# LEDs_Sheet_2.net
KiCad netlist of a schematic drawn in Altium Designer
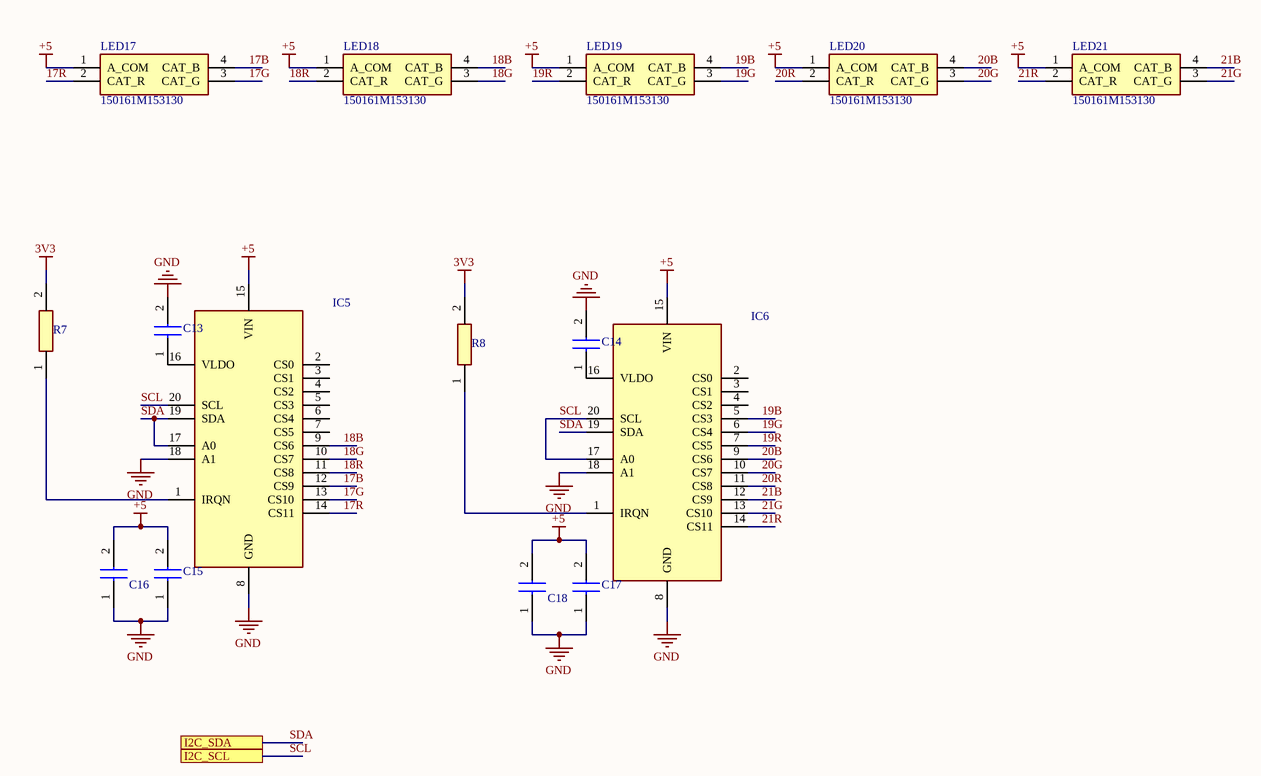
[diagram p0: LEDs_Sheet_2.SchDoc]

(export (version "E")
  (design (tool "Eeschema 10.0.6"))
  (components
    (comp (ref "C13")
      (value "C0402C105K9PAC")
      (footprint "SamacSys:CAPC1005X55N")
      (description "Capacitor")
      (fields (field (name "MOUSER PART NUMBER") "80-C0402C105K9PAC"))
      (libsource (lib "*") (part "C0402C105K9PAC"))
    )
    (comp (ref "C14")
      (value "C0402C105K9PAC")
      (footprint "SamacSys:CAPC1005X55N")
      (description "Capacitor")
      (fields (field (name "MOUSER PART NUMBER") "80-C0402C105K9PAC"))
      (libsource (lib "*") (part "C0402C105K9PAC"))
    )
    (comp (ref "C15")
      (value "C0402C105K9PAC")
      (footprint "SamacSys:CAPC1005X55N")
      (description "Capacitor")
      (fields (field (name "MOUSER PART NUMBER") "80-C0402C105K9PAC"))
      (libsource (lib "*") (part "C0402C105K9PAC"))
    )
    (comp (ref "C16")
      (value "C1005X7S1A225K050BC")
      (footprint "PcbLib:C1005_Commercial")
      (description "2µ2F 0402")
      (fields (field (name "MOUSER PART NUMBER") "810-C1005X7S1A225K"))
      (libsource (lib "Schlib") (part "C1005X7S1A225K050BC"))
    )
    (comp (ref "C17")
      (value "C0402C105K9PAC")
      (footprint "SamacSys:CAPC1005X55N")
      (description "Capacitor")
      (fields (field (name "MOUSER PART NUMBER") "80-C0402C105K9PAC"))
      (libsource (lib "*") (part "C0402C105K9PAC"))
    )
    (comp (ref "C18")
      (value "C1005X7S1A225K050BC")
      (footprint "PcbLib:C1005_Commercial")
      (description "2µ2F 0402")
      (fields (field (name "MOUSER PART NUMBER") "810-C1005X7S1A225K"))
      (libsource (lib "Schlib") (part "C1005X7S1A225K050BC"))
    )
    (comp (ref "IC5")
      (value "LED1202JR")
      (footprint "PcbLib:QFN20 3x3 (0,5mm pitch)")
      (description "Integrated Circuit")
      (fields (field (name "MOUSER PART NUMBER") "511-LED1202JR"))
      (libsource (lib "Schlib") (part "LED1202JR"))
    )
    (comp (ref "IC6")
      (value "LED1202JR")
      (footprint "PcbLib:QFN20 3x3 (0,5mm pitch)")
      (description "Integrated Circuit")
      (fields (field (name "MOUSER PART NUMBER") "511-LED1202JR"))
      (libsource (lib "Schlib") (part "LED1202JR"))
    )
    (comp (ref "LED17")
      (value "150161M153130")
      (footprint "PcbLib:150161M153130")
      (description "LED")
      (fields (field (name "MOUSER PART NUMBER") "710-150161M153130"))
      (libsource (lib "Schlib") (part "150161M153130"))
    )
    (comp (ref "LED18")
      (value "150161M153130")
      (footprint "PcbLib:150161M153130")
      (description "LED")
      (fields (field (name "MOUSER PART NUMBER") "710-150161M153130"))
      (libsource (lib "Schlib") (part "150161M153130"))
    )
    (comp (ref "LED19")
      (value "150161M153130")
      (footprint "PcbLib:150161M153130")
      (description "LED")
      (fields (field (name "MOUSER PART NUMBER") "710-150161M153130"))
      (libsource (lib "Schlib") (part "150161M153130"))
    )
    (comp (ref "LED20")
      (value "150161M153130")
      (footprint "PcbLib:150161M153130")
      (description "LED")
      (fields (field (name "MOUSER PART NUMBER") "710-150161M153130"))
      (libsource (lib "Schlib") (part "150161M153130"))
    )
    (comp (ref "LED21")
      (value "150161M153130")
      (footprint "PcbLib:150161M153130")
      (description "LED")
      (fields (field (name "MOUSER PART NUMBER") "710-150161M153130"))
      (libsource (lib "Schlib") (part "150161M153130"))
    )
    (comp (ref "R7")
      (value "MCS04020D1001BE000")
      (footprint "PcbLib:RESC1005X37N")
      (description "Resistor 1k 0402")
      (fields (field (name "MOUSER PART NUMBER") "594-MCS04020D1001BE0"))
      (libsource (lib "Schlib") (part "MCS04020D1001BE000"))
    )
    (comp (ref "R8")
      (value "MCS04020D1001BE000")
      (footprint "PcbLib:RESC1005X37N")
      (description "Resistor 1k 0402")
      (fields (field (name "MOUSER PART NUMBER") "594-MCS04020D1001BE0"))
      (libsource (lib "Schlib") (part "MCS04020D1001BE000"))
    )
  )
  (nets
    (net (code "1") (name "+5") (class "Default")
      (node (ref "C15") (pin "2") (pinfunction "2_2") (pintype "passive"))
      (node (ref "C16") (pin "2") (pinfunction "2_2") (pintype "passive"))
      (node (ref "C17") (pin "2") (pinfunction "2_2") (pintype "passive"))
      (node (ref "C18") (pin "2") (pinfunction "2_2") (pintype "passive"))
      (node (ref "IC5") (pin "15") (pinfunction "VIN_15") (pintype "passive"))
      (node (ref "IC6") (pin "15") (pinfunction "VIN_15") (pintype "passive"))
      (node (ref "LED17") (pin "1") (pinfunction "A_COM_1") (pintype "passive"))
      (node (ref "LED18") (pin "1") (pinfunction "A_COM_1") (pintype "passive"))
      (node (ref "LED19") (pin "1") (pinfunction "A_COM_1") (pintype "passive"))
      (node (ref "LED20") (pin "1") (pinfunction "A_COM_1") (pintype "passive"))
      (node (ref "LED21") (pin "1") (pinfunction "A_COM_1") (pintype "passive"))
    )
    (net (code "2") (name "/17B") (class "Default")
      (node (ref "IC5") (pin "12") (pinfunction "CS9_12") (pintype "passive"))
      (node (ref "LED17") (pin "4") (pinfunction "CAT_B_4") (pintype "passive"))
    )
    (net (code "3") (name "/17G") (class "Default")
      (node (ref "IC5") (pin "13") (pinfunction "CS10_13") (pintype "passive"))
      (node (ref "LED17") (pin "3") (pinfunction "CAT_G_3") (pintype "passive"))
    )
    (net (code "4") (name "/17R") (class "Default")
      (node (ref "IC5") (pin "14") (pinfunction "CS11_14") (pintype "passive"))
      (node (ref "LED17") (pin "2") (pinfunction "CAT_R_2") (pintype "passive"))
    )
    (net (code "5") (name "/18B") (class "Default")
      (node (ref "IC5") (pin "9") (pinfunction "CS6_9") (pintype "passive"))
      (node (ref "LED18") (pin "4") (pinfunction "CAT_B_4") (pintype "passive"))
    )
    (net (code "6") (name "/18G") (class "Default")
      (node (ref "IC5") (pin "10") (pinfunction "CS7_10") (pintype "passive"))
      (node (ref "LED18") (pin "3") (pinfunction "CAT_G_3") (pintype "passive"))
    )
    (net (code "7") (name "/18R") (class "Default")
      (node (ref "IC5") (pin "11") (pinfunction "CS8_11") (pintype "passive"))
      (node (ref "LED18") (pin "2") (pinfunction "CAT_R_2") (pintype "passive"))
    )
    (net (code "8") (name "/19B") (class "Default")
      (node (ref "IC6") (pin "5") (pinfunction "CS3_5") (pintype "passive"))
      (node (ref "LED19") (pin "4") (pinfunction "CAT_B_4") (pintype "passive"))
    )
    (net (code "9") (name "/19G") (class "Default")
      (node (ref "IC6") (pin "6") (pinfunction "CS4_6") (pintype "passive"))
      (node (ref "LED19") (pin "3") (pinfunction "CAT_G_3") (pintype "passive"))
    )
    (net (code "10") (name "/19R") (class "Default")
      (node (ref "IC6") (pin "7") (pinfunction "CS5_7") (pintype "passive"))
      (node (ref "LED19") (pin "2") (pinfunction "CAT_R_2") (pintype "passive"))
    )
    (net (code "11") (name "/20B") (class "Default")
      (node (ref "IC6") (pin "9") (pinfunction "CS6_9") (pintype "passive"))
      (node (ref "LED20") (pin "4") (pinfunction "CAT_B_4") (pintype "passive"))
    )
    (net (code "12") (name "/20G") (class "Default")
      (node (ref "IC6") (pin "10") (pinfunction "CS7_10") (pintype "passive"))
      (node (ref "LED20") (pin "3") (pinfunction "CAT_G_3") (pintype "passive"))
    )
    (net (code "13") (name "/20R") (class "Default")
      (node (ref "IC6") (pin "11") (pinfunction "CS8_11") (pintype "passive"))
      (node (ref "LED20") (pin "2") (pinfunction "CAT_R_2") (pintype "passive"))
    )
    (net (code "14") (name "/21B") (class "Default")
      (node (ref "IC6") (pin "12") (pinfunction "CS9_12") (pintype "passive"))
      (node (ref "LED21") (pin "4") (pinfunction "CAT_B_4") (pintype "passive"))
    )
    (net (code "15") (name "/21G") (class "Default")
      (node (ref "IC6") (pin "13") (pinfunction "CS10_13") (pintype "passive"))
      (node (ref "LED21") (pin "3") (pinfunction "CAT_G_3") (pintype "passive"))
    )
    (net (code "16") (name "/21R") (class "Default")
      (node (ref "IC6") (pin "14") (pinfunction "CS11_14") (pintype "passive"))
      (node (ref "LED21") (pin "2") (pinfunction "CAT_R_2") (pintype "passive"))
    )
    (net (code "17") (name "/SCL") (class "Default")
      (node (ref "IC5") (pin "20") (pinfunction "SCL_20") (pintype "passive"))
      (node (ref "IC6") (pin "17") (pinfunction "A0_17") (pintype "passive"))
      (node (ref "IC6") (pin "20") (pinfunction "SCL_20") (pintype "passive"))
    )
    (net (code "18") (name "/SDA") (class "Default")
      (node (ref "IC5") (pin "17") (pinfunction "A0_17") (pintype "passive"))
      (node (ref "IC5") (pin "19") (pinfunction "SDA_19") (pintype "passive"))
      (node (ref "IC6") (pin "19") (pinfunction "SDA_19") (pintype "passive"))
    )
    (net (code "19") (name "3V3") (class "Default")
      (node (ref "R7") (pin "2") (pinfunction "2_2") (pintype "passive"))
      (node (ref "R8") (pin "2") (pinfunction "2_2") (pintype "passive"))
    )
    (net (code "20") (name "GND") (class "Default")
      (node (ref "C13") (pin "2") (pinfunction "2_2") (pintype "passive"))
      (node (ref "C14") (pin "2") (pinfunction "2_2") (pintype "passive"))
      (node (ref "C15") (pin "1") (pinfunction "1_1") (pintype "passive"))
      (node (ref "C16") (pin "1") (pinfunction "1_1") (pintype "passive"))
      (node (ref "C17") (pin "1") (pinfunction "1_1") (pintype "passive"))
      (node (ref "C18") (pin "1") (pinfunction "1_1") (pintype "passive"))
      (node (ref "IC5") (pin "18") (pinfunction "A1_18") (pintype "passive"))
      (node (ref "IC5") (pin "8") (pinfunction "GND_8") (pintype "passive"))
      (node (ref "IC6") (pin "18") (pinfunction "A1_18") (pintype "passive"))
      (node (ref "IC6") (pin "8") (pinfunction "GND_8") (pintype "passive"))
    )
    (net (code "21") (name "Net-(IC5-IRQN)") (class "Default")
      (node (ref "IC5") (pin "1") (pinfunction "IRQN_1") (pintype "passive"))
      (node (ref "R7") (pin "1") (pinfunction "1_1") (pintype "passive"))
    )
    (net (code "22") (name "Net-(IC5-VLDO)") (class "Default")
      (node (ref "C13") (pin "1") (pinfunction "1_1") (pintype "passive"))
      (node (ref "IC5") (pin "16") (pinfunction "VLDO_16") (pintype "passive"))
    )
    (net (code "23") (name "Net-(IC6-IRQN)") (class "Default")
      (node (ref "IC6") (pin "1") (pinfunction "IRQN_1") (pintype "passive"))
      (node (ref "R8") (pin "1") (pinfunction "1_1") (pintype "passive"))
    )
    (net (code "24") (name "Net-(IC6-VLDO)") (class "Default")
      (node (ref "C14") (pin "1") (pinfunction "1_1") (pintype "passive"))
      (node (ref "IC6") (pin "16") (pinfunction "VLDO_16") (pintype "passive"))
    )
    (net (code "25") (name "unconnected-(IC5-CS0-Pad2)") (class "Default")
      (node (ref "IC5") (pin "2") (pinfunction "CS0_2") (pintype "passive"))
    )
    (net (code "26") (name "unconnected-(IC5-CS1-Pad3)") (class "Default")
      (node (ref "IC5") (pin "3") (pinfunction "CS1_3") (pintype "passive"))
    )
    (net (code "27") (name "unconnected-(IC5-CS2-Pad4)") (class "Default")
      (node (ref "IC5") (pin "4") (pinfunction "CS2_4") (pintype "passive"))
    )
    (net (code "28") (name "unconnected-(IC5-CS3-Pad5)") (class "Default")
      (node (ref "IC5") (pin "5") (pinfunction "CS3_5") (pintype "passive"))
    )
    (net (code "29") (name "unconnected-(IC5-CS4-Pad6)") (class "Default")
      (node (ref "IC5") (pin "6") (pinfunction "CS4_6") (pintype "passive"))
    )
    (net (code "30") (name "unconnected-(IC5-CS5-Pad7)") (class "Default")
      (node (ref "IC5") (pin "7") (pinfunction "CS5_7") (pintype "passive"))
    )
    (net (code "31") (name "unconnected-(IC6-CS0-Pad2)") (class "Default")
      (node (ref "IC6") (pin "2") (pinfunction "CS0_2") (pintype "passive"))
    )
    (net (code "32") (name "unconnected-(IC6-CS1-Pad3)") (class "Default")
      (node (ref "IC6") (pin "3") (pinfunction "CS1_3") (pintype "passive"))
    )
    (net (code "33") (name "unconnected-(IC6-CS2-Pad4)") (class "Default")
      (node (ref "IC6") (pin "4") (pinfunction "CS2_4") (pintype "passive"))
    )
  )
)
